# SHT_Test_Module.net
KiCad netlist of a schematic drawn in EAGLE
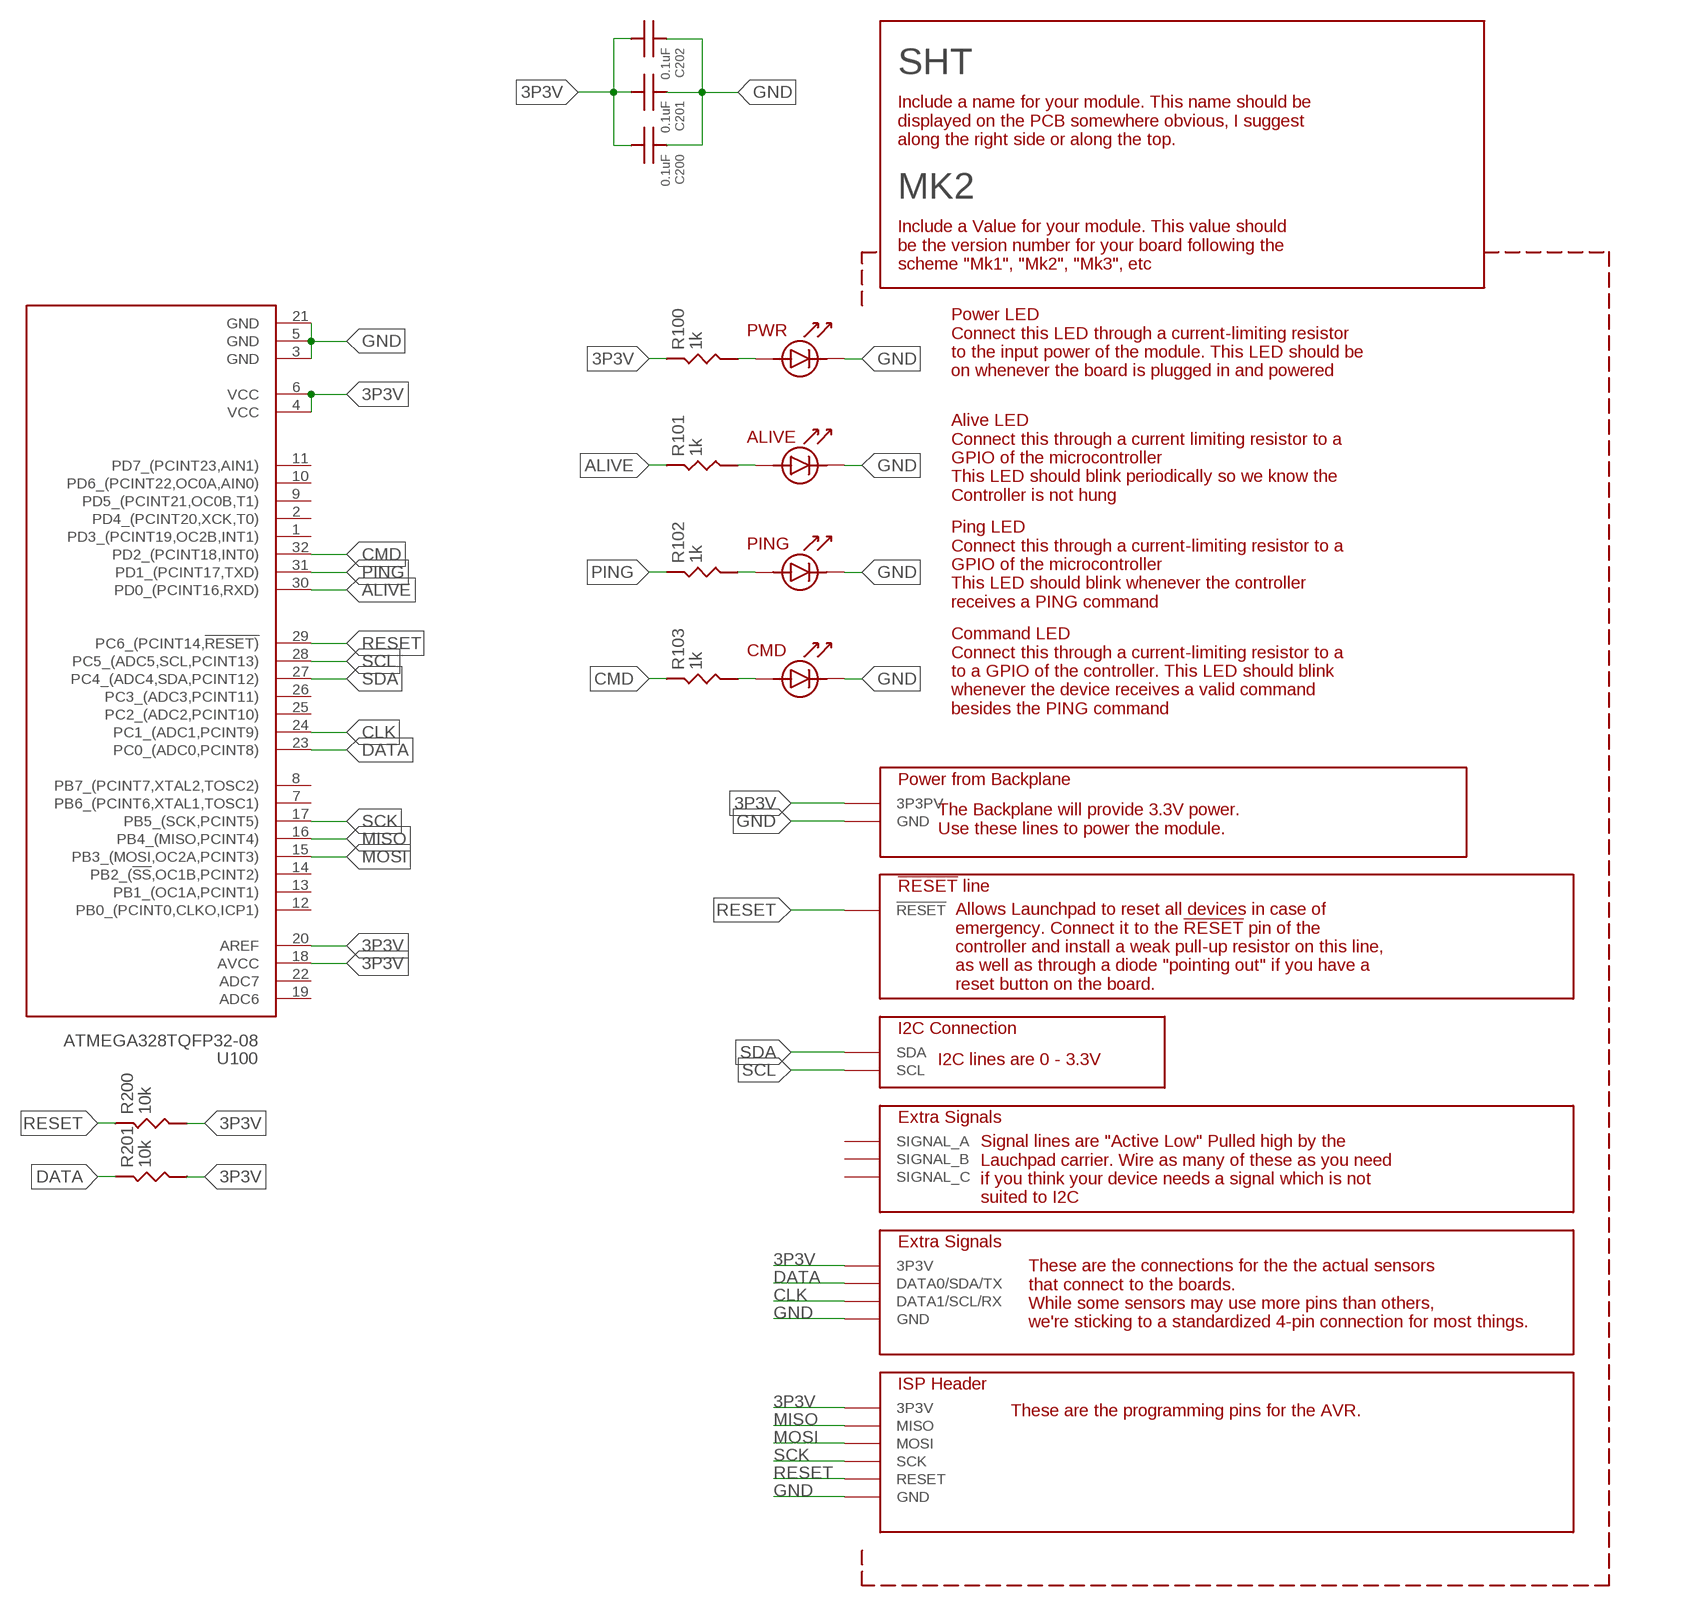
[diagram p0: schematic, sheet 1]

(export (version "E")
  (design (tool "Eeschema 10.0.6"))
  (components
    (comp (ref "C200")
      (value "0.1uF")
      (footprint "eagle-import:0805_STACKPOLERESISTOR")
      (libsource (lib "eagle-import") (part "CAPACITOR-UNPOLARIZED0805"))
    )
    (comp (ref "C201")
      (value "0.1uF")
      (footprint "eagle-import:0805_STACKPOLERESISTOR")
      (libsource (lib "eagle-import") (part "CAPACITOR-UNPOLARIZED0805"))
    )
    (comp (ref "C202")
      (value "0.1uF")
      (footprint "eagle-import:0805_STACKPOLERESISTOR")
      (libsource (lib "eagle-import") (part "CAPACITOR-UNPOLARIZED0805"))
    )
    (comp (ref "R100")
      (value "1k")
      (footprint "eagle-import:0805_STACKPOLERESISTOR")
      (libsource (lib "eagle-import") (part "RESISTOR"))
    )
    (comp (ref "R101")
      (value "1k")
      (footprint "eagle-import:0805_STACKPOLERESISTOR")
      (libsource (lib "eagle-import") (part "RESISTOR"))
    )
    (comp (ref "R102")
      (value "1k")
      (footprint "eagle-import:0805_STACKPOLERESISTOR")
      (libsource (lib "eagle-import") (part "RESISTOR"))
    )
    (comp (ref "R103")
      (value "1k")
      (footprint "eagle-import:0805_STACKPOLERESISTOR")
      (libsource (lib "eagle-import") (part "RESISTOR"))
    )
    (comp (ref "R200")
      (value "10k")
      (footprint "eagle-import:0805_STACKPOLERESISTOR")
      (libsource (lib "eagle-import") (part "RESISTOR"))
    )
    (comp (ref "R201")
      (value "10k")
      (footprint "eagle-import:0805_STACKPOLERESISTOR")
      (libsource (lib "eagle-import") (part "RESISTOR"))
    )
    (comp (ref "SHT")
      (value "MK2")
      (footprint "eagle-import:SENSOR_MODULE_MK1")
      (libsource (lib "eagle-import") (part "SENSOR_MODULE_MK1"))
    )
    (comp (ref "U100")
      (value "ATMEGA328TQFP32-08")
      (footprint "eagle-import:TQFP32-08")
      (libsource (lib "eagle-import") (part "ATMEGA328TQFP32-08"))
    )
  )
  (nets
    (net (code "1") (name "3P3V") (class "Default")
      (node (ref "C200") (pin "P$2") (pinfunction "P$2_P$2") (pintype "bidirectional"))
      (node (ref "C201") (pin "P$2") (pinfunction "P$2_P$2") (pintype "bidirectional"))
      (node (ref "C202") (pin "P$2") (pinfunction "P$2_P$2") (pintype "bidirectional"))
      (node (ref "R100") (pin "P$1") (pinfunction "P$1_P$1") (pintype "bidirectional"))
      (node (ref "R200") (pin "P$2") (pinfunction "P$2_P$2") (pintype "bidirectional"))
      (node (ref "R201") (pin "P$2") (pinfunction "P$2_P$2") (pintype "bidirectional"))
      (node (ref "SHT") (pin "3P3V@1") (pinfunction "3P3PV_3P3V@1") (pintype "bidirectional"))
      (node (ref "SHT") (pin "3P3V@2") (pinfunction "3P3V_3P3V@2") (pintype "bidirectional"))
      (node (ref "SHT") (pin "3P3V@3") (pinfunction "3P3V_3P3V@3") (pintype "bidirectional"))
      (node (ref "SHT") (pin "3P3V@4") (pinfunction "3P3V_3P3V@4") (pintype "bidirectional"))
      (node (ref "U100") (pin "18") (pinfunction "AVCC_18") (pintype "bidirectional"))
      (node (ref "U100") (pin "20") (pinfunction "AREF_20") (pintype "bidirectional"))
      (node (ref "U100") (pin "4") (pinfunction "VCC_4") (pintype "bidirectional"))
      (node (ref "U100") (pin "6") (pinfunction "VCC_6") (pintype "bidirectional"))
    )
    (net (code "2") (name "ALIVE") (class "Default")
      (node (ref "R101") (pin "P$1") (pinfunction "P$1_P$1") (pintype "bidirectional"))
      (node (ref "U100") (pin "30") (pinfunction "PD0_(PCINT16,RXD)_30") (pintype "bidirectional"))
    )
    (net (code "3") (name "CLK") (class "Default")
      (node (ref "SHT") (pin "DATA1@1") (pinfunction "DATA1/SCL/RX_DATA1@1") (pintype "bidirectional"))
      (node (ref "SHT") (pin "DATA1@2") (pinfunction "DATA1/SCL/RX_DATA1@2") (pintype "bidirectional"))
      (node (ref "U100") (pin "24") (pinfunction "PC1_(ADC1,PCINT9)_24") (pintype "bidirectional"))
    )
    (net (code "4") (name "CMD") (class "Default")
      (node (ref "R103") (pin "P$1") (pinfunction "P$1_P$1") (pintype "bidirectional"))
      (node (ref "U100") (pin "32") (pinfunction "PD2_(PCINT18,INT0)_32") (pintype "bidirectional"))
    )
    (net (code "5") (name "DATA") (class "Default")
      (node (ref "R201") (pin "P$1") (pinfunction "P$1_P$1") (pintype "bidirectional"))
      (node (ref "SHT") (pin "DATA0@1") (pinfunction "DATA0/SDA/TX_DATA0@1") (pintype "bidirectional"))
      (node (ref "SHT") (pin "DATA0@2") (pinfunction "DATA0/SDA/TX_DATA0@2") (pintype "bidirectional"))
      (node (ref "U100") (pin "23") (pinfunction "PC0_(ADC0,PCINT8)_23") (pintype "bidirectional"))
    )
    (net (code "6") (name "GND") (class "Default")
      (node (ref "C200") (pin "P$1") (pinfunction "P$1_P$1") (pintype "bidirectional"))
      (node (ref "C201") (pin "P$1") (pinfunction "P$1_P$1") (pintype "bidirectional"))
      (node (ref "C202") (pin "P$1") (pinfunction "P$1_P$1") (pintype "bidirectional"))
      (node (ref "SHT") (pin "ALIVELED_CATHODE") (pinfunction "ALIVELED_CATHODE_ALIVELED_CATHODE") (pintype "bidirectional"))
      (node (ref "SHT") (pin "CMDLED_CATHODE") (pinfunction "CMDLED_CATHODE_CMDLED_CATHODE") (pintype "bidirectional"))
      (node (ref "SHT") (pin "GND@1") (pinfunction "GND_GND@1") (pintype "bidirectional"))
      (node (ref "SHT") (pin "GND@2") (pinfunction "GND_GND@2") (pintype "bidirectional"))
      (node (ref "SHT") (pin "GND@3") (pinfunction "GND_GND@3") (pintype "bidirectional"))
      (node (ref "SHT") (pin "GND@4") (pinfunction "GND_GND@4") (pintype "bidirectional"))
      (node (ref "SHT") (pin "PINGLED_CATHODE") (pinfunction "PINGLED_CATHODE_PINGLED_CATHODE") (pintype "bidirectional"))
      (node (ref "SHT") (pin "PWRLED_CATHODE") (pinfunction "PWRLED_CATHODE_PWRLED_CATHODE") (pintype "bidirectional"))
      (node (ref "U100") (pin "21") (pinfunction "GND_21") (pintype "bidirectional"))
      (node (ref "U100") (pin "3") (pinfunction "GND_3") (pintype "bidirectional"))
      (node (ref "U100") (pin "5") (pinfunction "GND_5") (pintype "bidirectional"))
    )
    (net (code "7") (name "MISO") (class "Default")
      (node (ref "SHT") (pin "MISO") (pinfunction "MISO_MISO") (pintype "bidirectional"))
      (node (ref "U100") (pin "16") (pinfunction "PB4_(MISO,PCINT4)_16") (pintype "bidirectional"))
    )
    (net (code "8") (name "MOSI") (class "Default")
      (node (ref "SHT") (pin "MOSI") (pinfunction "MOSI_MOSI") (pintype "bidirectional"))
      (node (ref "U100") (pin "15") (pinfunction "PB3_(MOSI,OC2A,PCINT3)_15") (pintype "bidirectional"))
    )
    (net (code "9") (name "Net-(R100-PadP$2)") (class "Default")
      (node (ref "R100") (pin "P$2") (pinfunction "P$2_P$2") (pintype "bidirectional"))
      (node (ref "SHT") (pin "PWRLED_ANODE") (pinfunction "PWRLED_ANODE_PWRLED_ANODE") (pintype "bidirectional"))
    )
    (net (code "10") (name "Net-(R101-PadP$2)") (class "Default")
      (node (ref "R101") (pin "P$2") (pinfunction "P$2_P$2") (pintype "bidirectional"))
      (node (ref "SHT") (pin "ALIVELED_ANODE") (pinfunction "ALIVELED_ANODE_ALIVELED_ANODE") (pintype "bidirectional"))
    )
    (net (code "11") (name "Net-(R102-PadP$2)") (class "Default")
      (node (ref "R102") (pin "P$2") (pinfunction "P$2_P$2") (pintype "bidirectional"))
      (node (ref "SHT") (pin "PINGLED_ANODE") (pinfunction "PINGLED_ANODE_PINGLED_ANODE") (pintype "bidirectional"))
    )
    (net (code "12") (name "Net-(R103-PadP$2)") (class "Default")
      (node (ref "R103") (pin "P$2") (pinfunction "P$2_P$2") (pintype "bidirectional"))
      (node (ref "SHT") (pin "CMDLED_ANODE") (pinfunction "CMDLED_ANODE_CMDLED_ANODE") (pintype "bidirectional"))
    )
    (net (code "13") (name "PING") (class "Default")
      (node (ref "R102") (pin "P$1") (pinfunction "P$1_P$1") (pintype "bidirectional"))
      (node (ref "U100") (pin "31") (pinfunction "PD1_(PCINT17,TXD)_31") (pintype "bidirectional"))
    )
    (net (code "14") (name "RESET") (class "Default")
      (node (ref "R200") (pin "P$1") (pinfunction "P$1_P$1") (pintype "bidirectional"))
      (node (ref "SHT") (pin "RESET@1") (pinfunction "~{RESET}_RESET@1") (pintype "bidirectional"))
      (node (ref "SHT") (pin "RESET@2") (pinfunction "RESET_RESET@2") (pintype "bidirectional"))
      (node (ref "U100") (pin "29") (pinfunction "PC6_(PCINT14,~{RESET})_29") (pintype "bidirectional"))
    )
    (net (code "15") (name "SCK") (class "Default")
      (node (ref "SHT") (pin "SCK") (pinfunction "SCK_SCK") (pintype "bidirectional"))
      (node (ref "U100") (pin "17") (pinfunction "PB5_(SCK,PCINT5)_17") (pintype "bidirectional"))
    )
    (net (code "16") (name "SCL") (class "Default")
      (node (ref "SHT") (pin "SCL") (pinfunction "SCL_SCL") (pintype "bidirectional"))
      (node (ref "U100") (pin "28") (pinfunction "PC5_(ADC5,SCL,PCINT13)_28") (pintype "bidirectional"))
    )
    (net (code "17") (name "SDA") (class "Default")
      (node (ref "SHT") (pin "SDA") (pinfunction "SDA_SDA") (pintype "bidirectional"))
      (node (ref "U100") (pin "27") (pinfunction "PC4_(ADC4,SDA,PCINT12)_27") (pintype "bidirectional"))
    )
    (net (code "18") (name "unconnected-(SHT-SIGNAL_A-PadA)") (class "Default")
      (node (ref "SHT") (pin "A") (pinfunction "SIGNAL_A_A") (pintype "bidirectional"))
    )
    (net (code "19") (name "unconnected-(SHT-SIGNAL_B-PadB)") (class "Default")
      (node (ref "SHT") (pin "B") (pinfunction "SIGNAL_B_B") (pintype "bidirectional"))
    )
    (net (code "20") (name "unconnected-(SHT-SIGNAL_C-PadC)") (class "Default")
      (node (ref "SHT") (pin "C") (pinfunction "SIGNAL_C_C") (pintype "bidirectional"))
    )
    (net (code "21") (name "unconnected-(U100-ADC6-Pad19)") (class "Default")
      (node (ref "U100") (pin "19") (pinfunction "ADC6_19") (pintype "bidirectional"))
    )
    (net (code "22") (name "unconnected-(U100-ADC7-Pad22)") (class "Default")
      (node (ref "U100") (pin "22") (pinfunction "ADC7_22") (pintype "bidirectional"))
    )
    (net (code "23") (name "unconnected-(U100-PB0_(PCINT0,CLKO,ICP1)-Pad12)") (class "Default")
      (node (ref "U100") (pin "12") (pinfunction "PB0_(PCINT0,CLKO,ICP1)_12") (pintype "bidirectional"))
    )
    (net (code "24") (name "unconnected-(U100-PB1_(OC1A,PCINT1)-Pad13)") (class "Default")
      (node (ref "U100") (pin "13") (pinfunction "PB1_(OC1A,PCINT1)_13") (pintype "bidirectional"))
    )
    (net (code "25") (name "unconnected-(U100-PB2_(~{SS,OC1B,PCINT2})-Pad14)") (class "Default")
      (node (ref "U100") (pin "14") (pinfunction "PB2_(~{SS,OC1B,PCINT2})_14") (pintype "bidirectional"))
    )
    (net (code "26") (name "unconnected-(U100-PB6_(PCINT6,XTAL1,TOSC1)-Pad7)") (class "Default")
      (node (ref "U100") (pin "7") (pinfunction "PB6_(PCINT6,XTAL1,TOSC1)_7") (pintype "bidirectional"))
    )
    (net (code "27") (name "unconnected-(U100-PB7_(PCINT7,XTAL2,TOSC2)-Pad8)") (class "Default")
      (node (ref "U100") (pin "8") (pinfunction "PB7_(PCINT7,XTAL2,TOSC2)_8") (pintype "bidirectional"))
    )
    (net (code "28") (name "unconnected-(U100-PC2_(ADC2,PCINT10)-Pad25)") (class "Default")
      (node (ref "U100") (pin "25") (pinfunction "PC2_(ADC2,PCINT10)_25") (pintype "bidirectional"))
    )
    (net (code "29") (name "unconnected-(U100-PC3_(ADC3,PCINT11)-Pad26)") (class "Default")
      (node (ref "U100") (pin "26") (pinfunction "PC3_(ADC3,PCINT11)_26") (pintype "bidirectional"))
    )
    (net (code "30") (name "unconnected-(U100-PD3_(PCINT19,OC2B,INT1)-Pad1)") (class "Default")
      (node (ref "U100") (pin "1") (pinfunction "PD3_(PCINT19,OC2B,INT1)_1") (pintype "bidirectional"))
    )
    (net (code "31") (name "unconnected-(U100-PD4_(PCINT20,XCK,T0)-Pad2)") (class "Default")
      (node (ref "U100") (pin "2") (pinfunction "PD4_(PCINT20,XCK,T0)_2") (pintype "bidirectional"))
    )
    (net (code "32") (name "unconnected-(U100-PD5_(PCINT21,OC0B,T1)-Pad9)") (class "Default")
      (node (ref "U100") (pin "9") (pinfunction "PD5_(PCINT21,OC0B,T1)_9") (pintype "bidirectional"))
    )
    (net (code "33") (name "unconnected-(U100-PD6_(PCINT22,OC0A,AIN0)-Pad10)") (class "Default")
      (node (ref "U100") (pin "10") (pinfunction "PD6_(PCINT22,OC0A,AIN0)_10") (pintype "bidirectional"))
    )
    (net (code "34") (name "unconnected-(U100-PD7_(PCINT23,AIN1)-Pad11)") (class "Default")
      (node (ref "U100") (pin "11") (pinfunction "PD7_(PCINT23,AIN1)_11") (pintype "bidirectional"))
    )
  )
)
